# RTD.net
KiCad netlist of a schematic drawn in Altium Designer
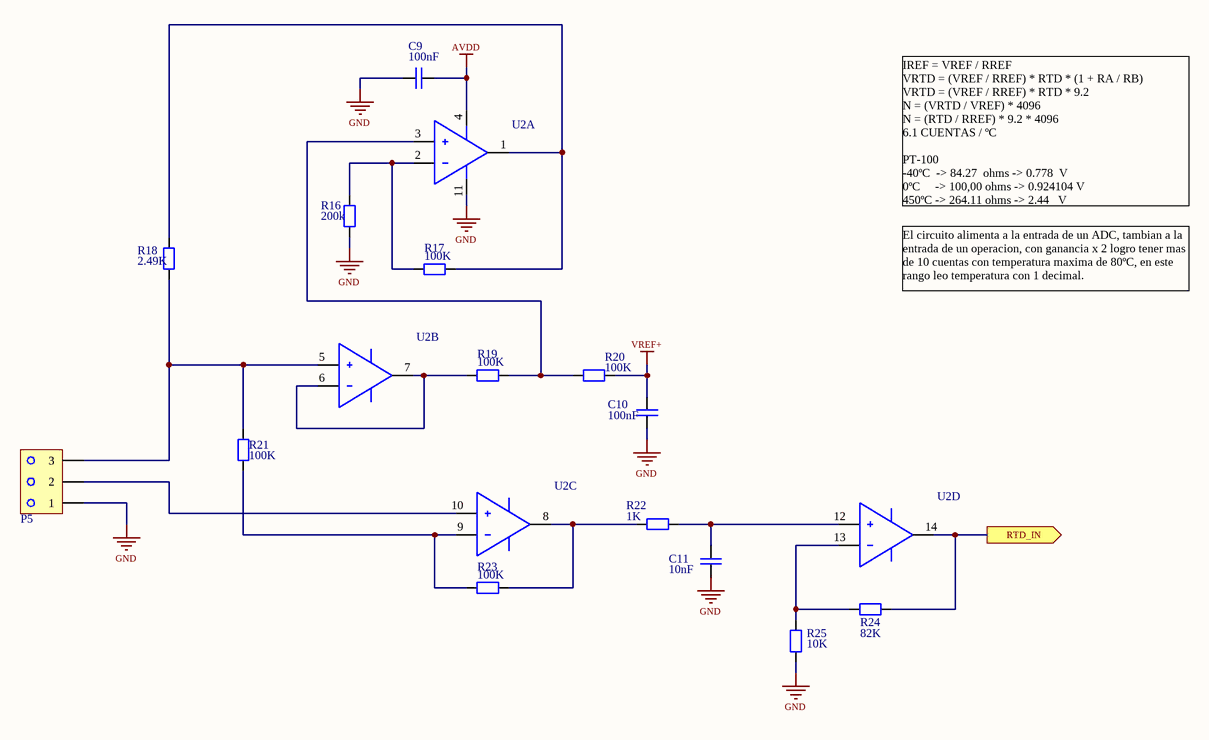
[diagram p0: RTD.SchDoc]

(export (version "E")
  (design (tool "Eeschema 10.0.6"))
  (components
    (comp (ref "C9")
      (value "100nF")
      (footprint "CAP_SM0805_YAGEOCC2_N")
      (description "CAP 100nF SM0805 X7R 25V YAGEO CC2")
      (fields
        (field (name "MANUFACTURER") "Yageo")
        (field (name "MANUFACTURER PART NUMBER") "CC0805KRX7R8BB104")
      )
      (libsource (lib "Yageo") (part "CC0805KRX7R8BB104"))
    )
    (comp (ref "C10")
      (value "100nF")
      (footprint "CAP_SM0805_YAGEOCC2_N")
      (description "CAP 100nF SM0805 X7R 25V YAGEO CC2")
      (fields
        (field (name "MANUFACTURER") "Yageo")
        (field (name "MANUFACTURER PART NUMBER") "CC0805KRX7R8BB104")
      )
      (libsource (lib "Yageo") (part "CC0805KRX7R8BB104"))
    )
    (comp (ref "C11")
      (value "10nF")
      (footprint "CAP_SM0805_YAGEOCC2_N")
      (description "CAP 10nF SM0805 X7R 25V YAGEO CC2")
      (fields
        (field (name "MANUFACTURER") "Yageo")
        (field (name "MANUFACTURER PART NUMBER") "CC0805KRX7R8BB103")
      )
      (libsource (lib "Yageo") (part "CC0805KRX7R8BB103"))
    )
    (comp (ref "P5")
      (value "WJ15EDGVC-3.81-3P")
      (footprint "HEADER PLUG 3")
      (description "TERM BLOK FEMALE 1X3 3.81MM")
      (fields (field (name "MANUFACTURER") "Ningbo Kangnex Elec"))
      (libsource (lib "plug") (part "WJ15EDGVC-3.81-3P"))
    )
    (comp (ref "R16")
      (value "200k")
      (footprint "RES_SM0805_YAGEORC_N")
      (description "RES 200K SM0805 YAGEO RC_L")
      (fields
        (field (name "MANUFACTURER") "Yageo")
        (field (name "MANUFACTURER PART NUMBER") "RC0805FR-07200KL")
      )
      (libsource (lib "Yageo") (part "RC0805FR-07200KL"))
    )
    (comp (ref "R17")
      (value "100K")
      (footprint "RES_SM0805_YAGEORC_N")
      (description "RES 100K SM0805 YAGEO RC_L")
      (fields
        (field (name "MANUFACTURER") "Yageo")
        (field (name "MANUFACTURER PART NUMBER") "RC0805FR-07100KL")
      )
      (libsource (lib "") (part "RC0805FR-07100KL_1"))
    )
    (comp (ref "R18")
      (value "2.49K")
      (footprint "RES_SM0805_YAGEORC_N")
      (description "RES 2K49 SM0805 YAGEO RT_L")
      (fields
        (field (name "MANUFACTURER") "Yageo")
        (field (name "MANUFACTURER PART NUMBER") "RC0603FR-072K49L")
      )
      (libsource (lib "Yageo") (part "RT0805FRE072K49L"))
    )
    (comp (ref "R19")
      (value "100K")
      (footprint "RES_SM0805_YAGEORC_N")
      (description "RES 100K SM0805 YAGEO RC_L")
      (fields
        (field (name "MANUFACTURER") "Yageo")
        (field (name "MANUFACTURER PART NUMBER") "RC0805FR-07100KL")
      )
      (libsource (lib "") (part "RC0805FR-07100KL_1"))
    )
    (comp (ref "R20")
      (value "100K")
      (footprint "RES_SM0805_YAGEORC_N")
      (description "RES 100K SM0805 YAGEO RC_L")
      (fields
        (field (name "MANUFACTURER") "Yageo")
        (field (name "MANUFACTURER PART NUMBER") "RC0805FR-07100KL")
      )
      (libsource (lib "") (part "RC0805FR-07100KL_1"))
    )
    (comp (ref "R21")
      (value "100K")
      (footprint "RES_SM0805_YAGEORC_N")
      (description "RES 100K SM0805 YAGEO RC_L")
      (fields
        (field (name "MANUFACTURER") "Yageo")
        (field (name "MANUFACTURER PART NUMBER") "RC0805FR-07100KL")
      )
      (libsource (lib "Yageo") (part "RC0805FR-07100KL"))
    )
    (comp (ref "R22")
      (value "1K")
      (footprint "RES_SM0805_YAGEORC_N")
      (description "RES 1K SM0805 YAGEO RC_L")
      (fields
        (field (name "MANUFACTURER") "Yageo")
        (field (name "MANUFACTURER PART NUMBER") "RC0805FR-071KL")
      )
      (libsource (lib "Yageo") (part "RC0805FR-071KL"))
    )
    (comp (ref "R23")
      (value "100K")
      (footprint "RES_SM0805_YAGEORC_N")
      (description "RES 100K SM0805 YAGEO RC_L")
      (fields
        (field (name "MANUFACTURER") "Yageo")
        (field (name "MANUFACTURER PART NUMBER") "RC0805FR-07100KL")
      )
      (libsource (lib "") (part "RC0805FR-07100KL_1"))
    )
    (comp (ref "R24")
      (value "82K")
      (footprint "RES_SM0805_YAGEORC_N")
      (description "RES 82K SM0805 YAGEO RC_L")
      (fields
        (field (name "MANUFACTURER") "Yageo")
        (field (name "MANUFACTURER PART NUMBER") "RC0805FR-0782KL")
      )
      (libsource (lib "Yageo") (part "RC0805FR-0782KL"))
    )
    (comp (ref "R25")
      (value "10K")
      (footprint "RES_SM0805_YAGEORC_N")
      (description "RES 10K SM0805 YAGEO RC_L")
      (fields
        (field (name "MANUFACTURER") "Yageo")
        (field (name "MANUFACTURER PART NUMBER") "RC0805FR-0710KL")
      )
      (libsource (lib "Yageo") (part "RC0805FR-0710KL"))
    )
    (comp (ref "U2")
      (value "GS8044")
      (footprint "GS8044-SR")
      (description "IC OPAMP GP 4 CIRCUIT 14SOIC")
      (fields (field (name "MANUFACTURER") "Gainsil") (field (name "MANUFACTURER PART NUMBER") "GS8044-SR"))
      (libsource (lib "OP_Amps") (part "GS8044-SR"))
    )
  )
  (nets
    (net (code "1") (name "/RTD_IN") (class "Default")
      (node (ref "R24") (pin "2") (pintype "passive"))
      (node (ref "U2") (pin "14") (pinfunction "VOUTD_14") (pintype "passive"))
    )
    (net (code "2") (name "AVDD") (class "Default")
      (node (ref "C9") (pin "1") (pintype "passive"))
      (node (ref "U2") (pin "4") (pinfunction "VDD_4") (pintype "power_in"))
    )
    (net (code "3") (name "GND") (class "Default")
      (node (ref "C10") (pin "2") (pintype "passive"))
      (node (ref "C11") (pin "2") (pintype "passive"))
      (node (ref "C9") (pin "2") (pintype "passive"))
      (node (ref "P5") (pin "1") (pinfunction "1_1") (pintype "passive"))
      (node (ref "R16") (pin "1") (pintype "passive"))
      (node (ref "R25") (pin "1") (pintype "passive"))
      (node (ref "U2") (pin "11") (pinfunction "VSS_11") (pintype "power_in"))
    )
    (net (code "4") (name "Net-(U2A-VINA+)") (class "Default")
      (node (ref "R19") (pin "2") (pintype "passive"))
      (node (ref "R20") (pin "1") (pintype "passive"))
      (node (ref "U2") (pin "3") (pinfunction "VINA+_3") (pintype "passive"))
    )
    (net (code "5") (name "Net-(U2A-VINA-)") (class "Default")
      (node (ref "R16") (pin "2") (pintype "passive"))
      (node (ref "R17") (pin "1") (pintype "passive"))
      (node (ref "U2") (pin "2") (pinfunction "VINA-_2") (pintype "passive"))
    )
    (net (code "6") (name "Net-(U2A-VOUTA)") (class "Default")
      (node (ref "R17") (pin "2") (pintype "passive"))
      (node (ref "R18") (pin "2") (pintype "passive"))
      (node (ref "U2") (pin "1") (pinfunction "VOUTA_1") (pintype "passive"))
    )
    (net (code "7") (name "Net-(U2B-VINB+)") (class "Default")
      (node (ref "P5") (pin "3") (pinfunction "3_3") (pintype "passive"))
      (node (ref "R18") (pin "1") (pintype "passive"))
      (node (ref "R21") (pin "2") (pintype "passive"))
      (node (ref "U2") (pin "5") (pinfunction "VINB+_5") (pintype "passive"))
    )
    (net (code "8") (name "Net-(U2B-VINB-)") (class "Default")
      (node (ref "R19") (pin "1") (pintype "passive"))
      (node (ref "U2") (pin "6") (pinfunction "VINB-_6") (pintype "passive"))
      (node (ref "U2") (pin "7") (pinfunction "VOUTB_7") (pintype "passive"))
    )
    (net (code "9") (name "Net-(U2C-VINC+)") (class "Default")
      (node (ref "P5") (pin "2") (pinfunction "2_2") (pintype "passive"))
      (node (ref "U2") (pin "10") (pinfunction "VINC+_10") (pintype "passive"))
    )
    (net (code "10") (name "Net-(U2C-VINC-)") (class "Default")
      (node (ref "R21") (pin "1") (pintype "passive"))
      (node (ref "R23") (pin "1") (pintype "passive"))
      (node (ref "U2") (pin "9") (pinfunction "VINC-_9") (pintype "passive"))
    )
    (net (code "11") (name "Net-(U2C-VOUTC)") (class "Default")
      (node (ref "R22") (pin "1") (pintype "passive"))
      (node (ref "R23") (pin "2") (pintype "passive"))
      (node (ref "U2") (pin "8") (pinfunction "VOUTC_8") (pintype "passive"))
    )
    (net (code "12") (name "Net-(U2D-VIND+)") (class "Default")
      (node (ref "C11") (pin "1") (pintype "passive"))
      (node (ref "R22") (pin "2") (pintype "passive"))
      (node (ref "U2") (pin "12") (pinfunction "VIND+_12") (pintype "passive"))
    )
    (net (code "13") (name "Net-(U2D-VIND-)") (class "Default")
      (node (ref "R24") (pin "1") (pintype "passive"))
      (node (ref "R25") (pin "2") (pintype "passive"))
      (node (ref "U2") (pin "13") (pinfunction "VIND-_13") (pintype "passive"))
    )
    (net (code "14") (name "VREF+") (class "Default")
      (node (ref "C10") (pin "1") (pintype "passive"))
      (node (ref "R20") (pin "2") (pintype "passive"))
    )
  )
)
